# Power-SMPS.net
KiCad netlist of a schematic drawn in Altium Designer
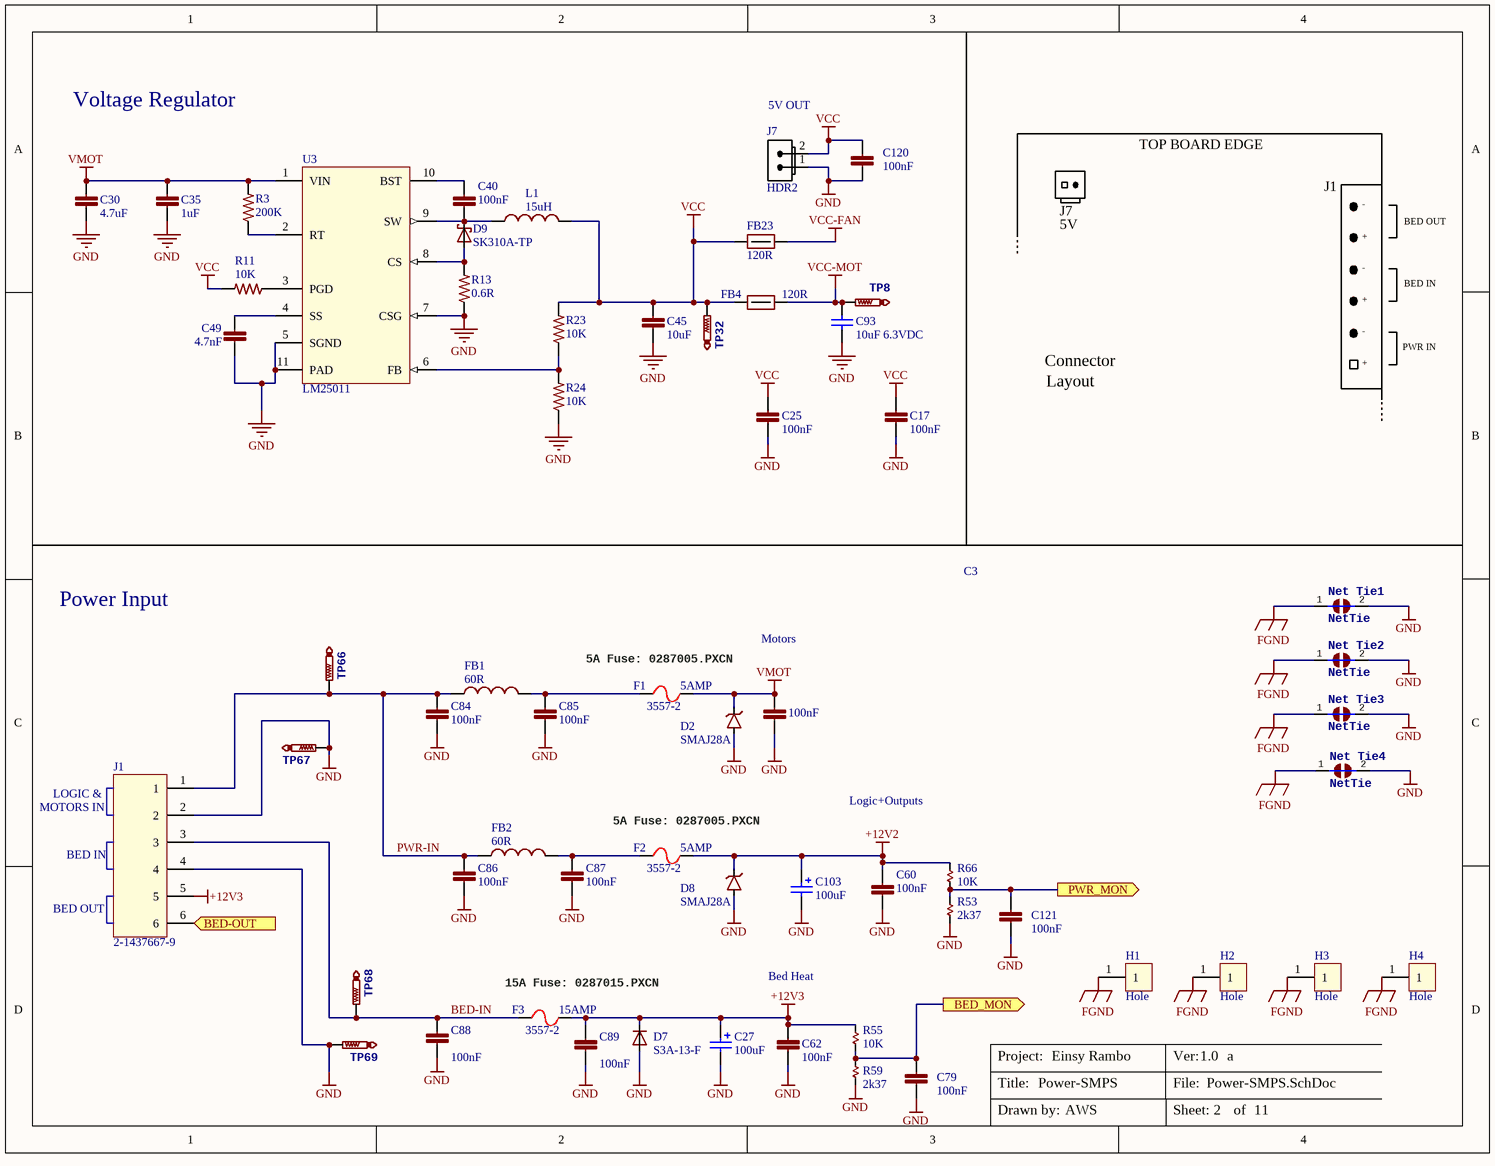
[diagram p0: Power-SMPS.SchDoc]

(export (version "E")
  (design (tool "Eeschema 10.0.6"))
  (components
    (comp (ref "C3")
      (value "100nF")
      (footprint "C0603")
      (description "CAP CER 0603 100nF 50V 10% X7R")
      (fields (field (name "MANUFACTURER") "Kemet") (field (name "TOLERANCE") "+/- 10%"))
      (libsource (lib "3Delight") (part "C0603C104K5RACTU"))
    )
    (comp (ref "C17")
      (value "100nF")
      (footprint "C0402")
      (description "CAP CER 0402 100nF 16V 10% X7R")
      (fields (field (name "MANUFACTURER") "Murata") (field (name "TOLERANCE") "+/- 10%"))
      (libsource (lib "") (part "GRM155R71C104KA88D_1"))
    )
    (comp (ref "C25")
      (value "100nF")
      (footprint "C0603")
      (description "CAP CER 0603 100nF 50V 10% X7R")
      (fields (field (name "MANUFACTURER") "Kemet") (field (name "TOLERANCE") "+/- 10%"))
      (libsource (lib "3Delight") (part "C0603C104K5RACTU"))
    )
    (comp (ref "C27")
      (value "100uF")
      (footprint "CAP-ELEC-063063077")
      (description "CAP ALUM 100UF 35V 20% SMD")
      (fields (field (name "MANUFACTURER") "Nichicon") (field (name "TOLERANCE") "+/- 20%"))
      (libsource (lib "3Delight") (part "UWT1V101MCL1GS"))
    )
    (comp (ref "C30")
      (value "4.7uF")
      (footprint "C1206")
      (description "CAP CER 1206 4.7uF 50V 10% X5R")
      (fields (field (name "MANUFACTURER") "Kemet") (field (name "TOLERANCE") "+/- 10%"))
      (libsource (lib "3Delight") (part "C1206C475K5PACTU"))
    )
    (comp (ref "C35")
      (value "1uF")
      (footprint "C0805")
      (description "CAP CER 0805 1uF 50V 10% X7R")
      (fields (field (name "MANUFACTURER") "Murata") (field (name "TOLERANCE") "+/- 10%"))
      (libsource (lib "3Delight") (part "GRM21BR71H105KA12L"))
    )
    (comp (ref "C40")
      (value "100nF")
      (footprint "C0603")
      (description "CAP CER 0603 100nF 50V 10% X7R")
      (fields (field (name "MANUFACTURER") "Kemet") (field (name "TOLERANCE") "+/- 10%"))
      (libsource (lib "3Delight") (part "C0603C104K5RACTU"))
    )
    (comp (ref "C45")
      (value "10uF")
      (footprint "C0805")
      (description "CAP CER 0805 10uF 10V 10% X5R")
      (fields (field (name "MANUFACTURER") "Kemet") (field (name "TOLERANCE") "+/- 10%"))
      (libsource (lib "3Delight") (part "C0805C106K8PACTU"))
    )
    (comp (ref "C49")
      (value "4.7nF")
      (footprint "C0402")
      (description "CAP CER 0402 4.7nF 25V 10% X7R")
      (fields (field (name "MANUFACTURER") "YAGEO") (field (name "TOLERANCE") "+/- 10%"))
      (libsource (lib "3Delight") (part "CC0402KRX7R8BB472"))
    )
    (comp (ref "C60")
      (value "100nF")
      (footprint "C0603")
      (description "CAP CER 0603 100nF 50V 10% X7R")
      (fields (field (name "MANUFACTURER") "Kemet") (field (name "TOLERANCE") "+/- 10%"))
      (libsource (lib "3Delight") (part "C0603C104K5RACTU"))
    )
    (comp (ref "C62")
      (value "100nF")
      (footprint "C0603")
      (description "CAP CER 0603 100nF 50V 10% X7R")
      (fields (field (name "MANUFACTURER") "Kemet") (field (name "TOLERANCE") "+/- 10%"))
      (libsource (lib "3Delight") (part "C0603C104K5RACTU"))
    )
    (comp (ref "C79")
      (value "100nF")
      (footprint "C0402")
      (description "CAP CER 0402 100nF 16V 10% X7R")
      (fields (field (name "MANUFACTURER") "Murata") (field (name "TOLERANCE") "+/- 10%"))
      (libsource (lib "3Delight") (part "GRM155R71C104KA88D"))
    )
    (comp (ref "C84")
      (value "100nF")
      (footprint "C0603")
      (description "CAP CER 0603 100nF 50V 10% X7R")
      (fields (field (name "MANUFACTURER") "Kemet") (field (name "TOLERANCE") "+/- 10%"))
      (libsource (lib "3Delight") (part "C0603C104K5RACTU"))
    )
    (comp (ref "C85")
      (value "100nF")
      (footprint "C0603")
      (description "CAP CER 0603 100nF 50V 10% X7R")
      (fields (field (name "MANUFACTURER") "Kemet") (field (name "TOLERANCE") "+/- 10%"))
      (libsource (lib "3Delight") (part "C0603C104K5RACTU"))
    )
    (comp (ref "C86")
      (value "100nF")
      (footprint "C0603")
      (description "CAP CER 0603 100nF 50V 10% X7R")
      (fields (field (name "MANUFACTURER") "Kemet") (field (name "TOLERANCE") "+/- 10%"))
      (libsource (lib "3Delight") (part "C0603C104K5RACTU"))
    )
    (comp (ref "C87")
      (value "100nF")
      (footprint "C0603")
      (description "CAP CER 0603 100nF 50V 10% X7R")
      (fields (field (name "MANUFACTURER") "Kemet") (field (name "TOLERANCE") "+/- 10%"))
      (libsource (lib "3Delight") (part "C0603C104K5RACTU"))
    )
    (comp (ref "C88")
      (value "100nF")
      (footprint "C0603")
      (description "CAP CER 0603 100nF 50V 10% X7R")
      (fields (field (name "MANUFACTURER") "Kemet") (field (name "TOLERANCE") "+/- 10%"))
      (libsource (lib "3Delight") (part "C0603C104K5RACTU"))
    )
    (comp (ref "C89")
      (value "100nF")
      (footprint "C0603")
      (description "CAP CER 0603 100nF 50V 10% X7R")
      (fields (field (name "MANUFACTURER") "Kemet") (field (name "TOLERANCE") "+/- 10%"))
      (libsource (lib "3Delight") (part "C0603C104K5RACTU"))
    )
    (comp (ref "C93")
      (value "10uF 6.3VDC")
      (footprint "C0603")
      (description "CAP CER 10UF 6.3V 10% JB 0603")
      (fields (field (name "TOLERANCE") "+/- 10%") (field (name "MANUFACTURER") "TDK"))
      (libsource (lib "Tigershark3D") (part "C1608JB0J106K080AB"))
    )
    (comp (ref "C103")
      (value "100uF")
      (footprint "CAP-ELEC-063063077")
      (description "CAP ALUM 100UF 35V 20% SMD")
      (fields (field (name "MANUFACTURER") "Nichicon") (field (name "TOLERANCE") "+/- 20%"))
      (libsource (lib "3Delight") (part "UWT1V101MCL1GS"))
    )
    (comp (ref "C120")
      (value "100nF")
      (footprint "C0402")
      (description "CAP CER 0402 100nF 16V 10% X7R")
      (fields (field (name "MANUFACTURER") "Murata") (field (name "TOLERANCE") "+/- 10%"))
      (libsource (lib "") (part "GRM155R71C104KA88D_2"))
    )
    (comp (ref "C121")
      (value "100nF")
      (footprint "C0402")
      (description "CAP CER 0402 100nF 16V 10% X7R")
      (fields (field (name "MANUFACTURER") "Murata") (field (name "TOLERANCE") "+/- 10%"))
      (libsource (lib "3Delight") (part "GRM155R71C104KA88D"))
    )
    (comp (ref "D2")
      (value "SMAJ28A")
      (footprint "SMA-SM")
      (description "TVS DIODE 28VWM 45.4VC SMA")
      (fields (field (name "MANUFACTURER") "Diodes Inc") (field (name "TOLERANCE") "NA"))
      (libsource (lib "Diodes") (part "SMAJ28A"))
    )
    (comp (ref "D7")
      (value "S3A-13-F")
      (footprint "DO-214AB")
      (description "DIODE DO-214AB")
      (fields (field (name "MANUFACTURER") "Diodes Incorporated") (field (name "TOLERANCE") "NA"))
      (libsource (lib "3Delight") (part "S3A-13-F"))
    )
    (comp (ref "D8")
      (value "SMAJ28A")
      (footprint "SMA-SM")
      (description "TVS DIODE 28VWM 45.4VC SMA")
      (fields (field (name "MANUFACTURER") "Diodes Inc") (field (name "TOLERANCE") "NA"))
      (libsource (lib "Diodes") (part "SMAJ28A"))
    )
    (comp (ref "D9")
      (value "SK310A-TP")
      (footprint "SMA-SM")
      (description "DIODE Schottky 3A SMA")
      (fields (field (name "MANUFACTURER") "MCC") (field (name "PART") "SK310A"))
      (libsource (lib "3Delight") (part "SK310A"))
    )
    (comp (ref "F1")
      (value "3557-2")
      (footprint "3557")
      (description "FUSE PTH ATO")
      (fields (field (name "MANUFACTURER") "Keystone") (field (name "PART") "Fuse"))
      (libsource (lib "3Delight") (part "3557-2"))
    )
    (comp (ref "F2")
      (value "3557-2")
      (footprint "3557")
      (description "FUSE PTH ATO")
      (fields (field (name "MANUFACTURER") "Keystone") (field (name "PART") "Fuse"))
      (libsource (lib "3Delight") (part "3557-2"))
    )
    (comp (ref "F3")
      (value "3557-2")
      (footprint "3557")
      (description "FUSE PTH ATO")
      (fields (field (name "MANUFACTURER") "Keystone") (field (name "PART") "Fuse"))
      (libsource (lib "3Delight") (part "3557-2"))
    )
    (comp (ref "FB1")
      (value "60R")
      (footprint "3Delight:L1806")
      (description "FERRITE BEAD 1806 60ohm")
      (fields (field (name "MANUFACTURER") "Murata") (field (name "PART") "60Rf"))
      (libsource (lib "3Delight") (part "BLM41PG600SN1L"))
    )
    (comp (ref "FB2")
      (value "60R")
      (footprint "3Delight:L1806")
      (description "FERRITE BEAD 1806 60ohm")
      (fields (field (name "MANUFACTURER") "Murata") (field (name "PART") "60Rf"))
      (libsource (lib "3Delight") (part "BLM41PG600SN1L"))
    )
    (comp (ref "FB4")
      (value "120R")
      (footprint "FB0603")
      (description "FERRITE BEAD 120 OHM 0603 1LN")
      (fields (field (name "MANUFACTURER") "Samsung") (field (name "PART") "FERRITE 120R 3A 0603"))
      (libsource (lib "3Delight") (part "FERRITE 220R 2.5A 0603"))
    )
    (comp (ref "FB23")
      (value "120R")
      (footprint "FB0603")
      (description "FERRITE BEAD 120 OHM 0603 1LN")
      (fields (field (name "MANUFACTURER") "Samsung") (field (name "PART") "FERRITE 120R 3A 0603"))
      (libsource (lib "Inductors") (part "FERRITE 120R 3A 0603"))
    )
    (comp (ref "H1")
      (value "Hole")
      (footprint "Wave_hole_3x7-singleSided")
      (libsource (lib "3Delight") (part "Hole"))
    )
    (comp (ref "H2")
      (value "Hole")
      (footprint "Wave_hole_3x7-singleSided")
      (libsource (lib "3Delight") (part "Hole"))
    )
    (comp (ref "H3")
      (value "Hole")
      (footprint "Wave_hole_3x7-singleSided")
      (libsource (lib "3Delight") (part "Hole"))
    )
    (comp (ref "H4")
      (value "Hole")
      (footprint "Wave_hole_3x7-singleSided")
      (libsource (lib "3Delight") (part "Hole"))
    )
    (comp (ref "J1")
      (value "2-1437667-9")
      (footprint "CON-Barrier-6-8.26mm")
      (description "CONN BARRIER STRIP 6CIRC 0.325\"")
      (fields (field (name "MANUFACTURER") "TE") (field (name "PART") "6POS"))
      (libsource (lib "3Delight") (part "2-1437667-9"))
    )
    (comp (ref "J7")
      (value "HDR2")
      (footprint "70543-02")
      (description "Connector 2pos")
      (fields (field (name "MANUFACTURER") "Molex") (field (name "PART") "10 Pin Conn"))
      (libsource (lib "Archim_0.4") (part "CONN 2PIN VERT 0.1{dblquote} SHRD LOCKING"))
    )
    (comp (ref "L1")
      (value "15uH")
      (footprint "XAL50xx_VLS6045")
      (description "FIXED IND 15UH 2.5A 98 MOHM SMD")
      (fields (field (name "MANUFACTURER") "TDK") (field (name "TOLERANCE") "+/- 20%"))
      (libsource (lib "3Delight") (part "IND 15uH 2.5A 0.075R"))
    )
    (comp (ref "Net Tie1")
      (value "NetTie")
      (footprint "Net Tie")
      (description "Net Tie")
      (fields (field (name "PUBLISHER") "UltiMachine"))
      (libsource (lib "3Delight") (part "NetTie"))
    )
    (comp (ref "Net Tie2")
      (value "NetTie")
      (footprint "Net Tie")
      (description "Net Tie")
      (fields (field (name "PUBLISHER") "UltiMachine"))
      (libsource (lib "3Delight") (part "NetTie"))
    )
    (comp (ref "Net Tie3")
      (value "NetTie")
      (footprint "Net Tie")
      (description "Net Tie")
      (fields (field (name "PUBLISHER") "UltiMachine"))
      (libsource (lib "3Delight") (part "NetTie"))
    )
    (comp (ref "Net Tie4")
      (value "NetTie")
      (footprint "Net Tie")
      (description "Net Tie")
      (fields (field (name "PUBLISHER") "UltiMachine"))
      (libsource (lib "3Delight") (part "NetTie"))
    )
    (comp (ref "R3")
      (value "200K")
      (footprint "R0402")
      (description "RES 0402 200K")
      (fields (field (name "MANUFACTURER") "Vishay Dale") (field (name "TOLERANCE") "+/- 1%"))
      (libsource (lib "3Delight") (part "CRCW0402200KFKED"))
    )
    (comp (ref "R11")
      (value "10K")
      (footprint "R0402")
      (description "RES SMD 10K OHM 1% 1/16W 0402")
      (fields (field (name "MANUFACTURER") "Yageo") (field (name "PART") "10k 1% 0402"))
      (libsource (lib "3Delight") (part "RC0402FR-0710KP"))
    )
    (comp (ref "R13")
      (value "0.6R")
      (footprint "2512R-0.55")
      (description "RES 0.06 OHM 1W 1% 2512 SMD")
      (fields (field (name "MANUFACTURER") "Yageo") (field (name "TOLERANCE") "1%"))
      (libsource (lib "3Delight") (part "RL2512FK-070R06L"))
    )
    (comp (ref "R23")
      (value "10K")
      (footprint "R0402")
      (description "RES SMD 10K OHM 1% 1/16W 0402")
      (fields (field (name "MANUFACTURER") "Yageo") (field (name "PART") "10k 1% 0402"))
      (libsource (lib "3Delight") (part "RC0402FR-0710KP"))
    )
    (comp (ref "R24")
      (value "10K")
      (footprint "R0402")
      (description "RES SMD 10K OHM 1% 1/16W 0402")
      (fields (field (name "MANUFACTURER") "Yageo") (field (name "PART") "10k 1% 0402"))
      (libsource (lib "3Delight") (part "RC0402FR-0710KP"))
    )
    (comp (ref "R53")
      (value "2k37")
      (footprint "R0402")
      (description "RES SMD 2.37K OHM 1% 1/16W 0402")
      (fields (field (name "MANUFACTURER") "Yageo") (field (name "PART") "2.37k"))
      (libsource (lib "3Delight") (part "RC0402FR-072K37L"))
    )
    (comp (ref "R55")
      (value "10K")
      (footprint "R0402")
      (description "RES SMD 10K OHM 1% 1/16W 0402")
      (fields (field (name "MANUFACTURER") "Yageo") (field (name "PART") "10k 1% 0402"))
      (libsource (lib "Resistors") (part "10k 1% 0402"))
    )
    (comp (ref "R59")
      (value "2k37")
      (footprint "R0402")
      (description "RES SMD 2.37K OHM 1% 1/16W 0402")
      (fields (field (name "MANUFACTURER") "Yageo") (field (name "PART") "2.37k"))
      (libsource (lib "3Delight") (part "RC0402FR-072K37L"))
    )
    (comp (ref "R66")
      (value "10K")
      (footprint "R0402")
      (description "RES SMD 10K OHM 1% 1/16W 0402")
      (fields (field (name "MANUFACTURER") "Yageo") (field (name "PART") "10k 1% 0402"))
      (libsource (lib "Resistors") (part "10k 1% 0402"))
    )
    (comp (ref "TP8")
      (value "TestPoint")
      (footprint "TP1-27")
      (description "Test Point")
      (libsource (lib "") (part "TestPoint_1"))
    )
    (comp (ref "TP32")
      (value "TestPoint")
      (footprint "TP1-27")
      (description "Test Point")
      (libsource (lib "3Delight") (part "TestPoint"))
    )
    (comp (ref "TP66")
      (value "TestPoint")
      (footprint "TP1-27")
      (description "Test Point")
      (libsource (lib "") (part "TestPoint_2"))
    )
    (comp (ref "TP67")
      (value "TestPoint")
      (footprint "TP1-27")
      (description "Test Point")
      (libsource (lib "") (part "TestPoint_3"))
    )
    (comp (ref "TP68")
      (value "TestPoint")
      (footprint "TP1-27")
      (description "Test Point")
      (libsource (lib "") (part "TestPoint_2"))
    )
    (comp (ref "TP69")
      (value "TestPoint")
      (footprint "TP1-27")
      (description "Test Point")
      (libsource (lib "") (part "TestPoint_1"))
    )
    (comp (ref "U3")
      (value "LM25011")
      (footprint "VSSOP10")
      (description "REG BUCK")
      (fields (field (name "MANUFACTURER") "TI") (field (name "TOLERANCE") "NA"))
      (libsource (lib "3Delight") (part "LM25011"))
    )
  )
  (nets
    (net (code "1") (name "+12V2") (class "Default")
      (node (ref "C103") (pin "1") (pinfunction "1_1") (pintype "passive"))
      (node (ref "C60") (pin "1") (pinfunction "1_1") (pintype "passive"))
      (node (ref "D8") (pin "K") (pinfunction "K_K") (pintype "passive"))
      (node (ref "F2") (pin "2") (pinfunction "2_2") (pintype "passive"))
      (node (ref "R66") (pin "2") (pinfunction "2_2") (pintype "passive"))
    )
    (net (code "2") (name "+12V3") (class "Default")
      (node (ref "C27") (pin "1") (pinfunction "1_1") (pintype "passive"))
      (node (ref "C62") (pin "1") (pinfunction "1_1") (pintype "passive"))
      (node (ref "C89") (pin "1") (pinfunction "1_1") (pintype "passive"))
      (node (ref "D7") (pin "C") (pinfunction "C_C") (pintype "passive"))
      (node (ref "F3") (pin "2") (pinfunction "2_2") (pintype "passive"))
      (node (ref "J1") (pin "5") (pinfunction "5_5") (pintype "passive"))
      (node (ref "R55") (pin "2") (pinfunction "2_2") (pintype "passive"))
    )
    (net (code "3") (name "/BED-IN") (class "Default")
      (node (ref "C88") (pin "1") (pinfunction "1_1") (pintype "passive"))
      (node (ref "F3") (pin "1") (pinfunction "1_1") (pintype "passive"))
      (node (ref "J1") (pin "3") (pinfunction "3_3") (pintype "passive"))
      (node (ref "TP68") (pin "TP") (pinfunction "TP_TP") (pintype "passive"))
    )
    (net (code "4") (name "/BED-OUT") (class "Default")
      (node (ref "J1") (pin "6") (pinfunction "6_6") (pintype "passive"))
    )
    (net (code "5") (name "/BED_MON") (class "Default")
      (node (ref "C79") (pin "1") (pinfunction "1_1") (pintype "passive"))
      (node (ref "R55") (pin "1") (pinfunction "1_1") (pintype "passive"))
      (node (ref "R59") (pin "1") (pinfunction "1_1") (pintype "passive"))
    )
    (net (code "6") (name "/PWR-IN") (class "Default")
      (node (ref "C84") (pin "1") (pinfunction "1_1") (pintype "passive"))
      (node (ref "C86") (pin "1") (pinfunction "1_1") (pintype "passive"))
      (node (ref "FB1") (pin "1") (pinfunction "1_1") (pintype "passive"))
      (node (ref "FB2") (pin "1") (pinfunction "1_1") (pintype "passive"))
      (node (ref "J1") (pin "1") (pinfunction "1_1") (pintype "passive"))
      (node (ref "TP66") (pin "TP") (pinfunction "TP_TP") (pintype "passive"))
    )
    (net (code "7") (name "/PWR_MON") (class "Default")
      (node (ref "C121") (pin "1") (pinfunction "1_1") (pintype "passive"))
      (node (ref "R53") (pin "1") (pinfunction "1_1") (pintype "passive"))
      (node (ref "R66") (pin "1") (pinfunction "1_1") (pintype "passive"))
    )
    (net (code "8") (name "FGND") (class "Default")
      (node (ref "H1") (pin "1") (pinfunction "1_1") (pintype "power_in"))
      (node (ref "H2") (pin "1") (pinfunction "1_1") (pintype "power_in"))
      (node (ref "H3") (pin "1") (pinfunction "1_1") (pintype "power_in"))
      (node (ref "H4") (pin "1") (pinfunction "1_1") (pintype "power_in"))
      (node (ref "Net Tie1") (pin "1") (pinfunction "1_1") (pintype "passive"))
      (node (ref "Net Tie2") (pin "1") (pinfunction "1_1") (pintype "passive"))
      (node (ref "Net Tie3") (pin "1") (pinfunction "1_1") (pintype "passive"))
      (node (ref "Net Tie4") (pin "1") (pinfunction "1_1") (pintype "passive"))
    )
    (net (code "9") (name "GND") (class "Default")
      (node (ref "C103") (pin "2") (pinfunction "2_2") (pintype "passive"))
      (node (ref "C120") (pin "1") (pinfunction "1_1") (pintype "passive"))
      (node (ref "C121") (pin "2") (pinfunction "2_2") (pintype "passive"))
      (node (ref "C17") (pin "2") (pinfunction "2_2") (pintype "passive"))
      (node (ref "C25") (pin "2") (pinfunction "2_2") (pintype "passive"))
      (node (ref "C27") (pin "2") (pinfunction "2_2") (pintype "passive"))
      (node (ref "C3") (pin "2") (pinfunction "2_2") (pintype "passive"))
      (node (ref "C30") (pin "2") (pinfunction "2_2") (pintype "passive"))
      (node (ref "C35") (pin "2") (pinfunction "2_2") (pintype "passive"))
      (node (ref "C45") (pin "2") (pinfunction "2_2") (pintype "passive"))
      (node (ref "C49") (pin "2") (pinfunction "2_2") (pintype "passive"))
      (node (ref "C60") (pin "2") (pinfunction "2_2") (pintype "passive"))
      (node (ref "C62") (pin "2") (pinfunction "2_2") (pintype "passive"))
      (node (ref "C79") (pin "2") (pinfunction "2_2") (pintype "passive"))
      (node (ref "C84") (pin "2") (pinfunction "2_2") (pintype "passive"))
      (node (ref "C85") (pin "2") (pinfunction "2_2") (pintype "passive"))
      (node (ref "C86") (pin "2") (pinfunction "2_2") (pintype "passive"))
      (node (ref "C87") (pin "2") (pinfunction "2_2") (pintype "passive"))
      (node (ref "C88") (pin "2") (pinfunction "2_2") (pintype "passive"))
      (node (ref "C89") (pin "2") (pinfunction "2_2") (pintype "passive"))
      (node (ref "C93") (pin "1") (pinfunction "1_1") (pintype "passive"))
      (node (ref "D2") (pin "A") (pinfunction "A_A") (pintype "passive"))
      (node (ref "D7") (pin "A") (pinfunction "A_A") (pintype "passive"))
      (node (ref "D8") (pin "A") (pinfunction "A_A") (pintype "passive"))
      (node (ref "J1") (pin "2") (pinfunction "2_2") (pintype "passive"))
      (node (ref "J1") (pin "4") (pinfunction "4_4") (pintype "passive"))
      (node (ref "J7") (pin "1") (pinfunction "S_1") (pintype "passive"))
      (node (ref "Net Tie1") (pin "2") (pinfunction "2_2") (pintype "passive"))
      (node (ref "Net Tie2") (pin "2") (pinfunction "2_2") (pintype "passive"))
      (node (ref "Net Tie3") (pin "2") (pinfunction "2_2") (pintype "passive"))
      (node (ref "Net Tie4") (pin "2") (pinfunction "2_2") (pintype "passive"))
      (node (ref "R13") (pin "1") (pinfunction "1_1") (pintype "passive"))
      (node (ref "R24") (pin "1") (pinfunction "1_1") (pintype "passive"))
      (node (ref "R53") (pin "2") (pinfunction "2_2") (pintype "passive"))
      (node (ref "R59") (pin "2") (pinfunction "2_2") (pintype "passive"))
      (node (ref "TP67") (pin "TP") (pinfunction "TP_TP") (pintype "passive"))
      (node (ref "TP69") (pin "TP") (pinfunction "TP_TP") (pintype "passive"))
      (node (ref "U3") (pin "11") (pinfunction "PAD_11") (pintype "power_in"))
      (node (ref "U3") (pin "5") (pinfunction "SGND_5") (pintype "power_in"))
      (node (ref "U3") (pin "7") (pinfunction "CSG_7") (pintype "input"))
    )
    (net (code "10") (name "Net-(C85-Pad1)") (class "Default")
      (node (ref "C85") (pin "1") (pinfunction "1_1") (pintype "passive"))
      (node (ref "F1") (pin "1") (pinfunction "1_1") (pintype "passive"))
      (node (ref "FB1") (pin "2") (pinfunction "2_2") (pintype "passive"))
    )
    (net (code "11") (name "Net-(C87-Pad1)") (class "Default")
      (node (ref "C87") (pin "1") (pinfunction "1_1") (pintype "passive"))
      (node (ref "F2") (pin "1") (pinfunction "1_1") (pintype "passive"))
      (node (ref "FB2") (pin "2") (pinfunction "2_2") (pintype "passive"))
    )
    (net (code "12") (name "Net-(U3-BST)") (class "Default")
      (node (ref "C40") (pin "1") (pinfunction "1_1") (pintype "passive"))
      (node (ref "U3") (pin "10") (pinfunction "BST_10") (pintype "power_in"))
    )
    (net (code "13") (name "Net-(U3-CS)") (class "Default")
      (node (ref "D9") (pin "A") (pinfunction "A_A") (pintype "passive"))
      (node (ref "R13") (pin "2") (pinfunction "2_2") (pintype "passive"))
      (node (ref "U3") (pin "8") (pinfunction "CS_8") (pintype "input"))
    )
    (net (code "14") (name "Net-(U3-FB)") (class "Default")
      (node (ref "R23") (pin "1") (pinfunction "1_1") (pintype "passive"))
      (node (ref "R24") (pin "2") (pinfunction "2_2") (pintype "passive"))
      (node (ref "U3") (pin "6") (pinfunction "FB_6") (pintype "input"))
    )
    (net (code "15") (name "Net-(U3-PGD)") (class "Default")
      (node (ref "R11") (pin "1") (pinfunction "1_1") (pintype "passive"))
      (node (ref "U3") (pin "3") (pinfunction "PGD_3") (pintype "power_in"))
    )
    (net (code "16") (name "Net-(U3-RT)") (class "Default")
      (node (ref "R3") (pin "1") (pinfunction "1_1") (pintype "passive"))
      (node (ref "U3") (pin "2") (pinfunction "RT_2") (pintype "power_in"))
    )
    (net (code "17") (name "Net-(U3-SS)") (class "Default")
      (node (ref "C49") (pin "1") (pinfunction "1_1") (pintype "passive"))
      (node (ref "U3") (pin "4") (pinfunction "SS_4") (pintype "power_in"))
    )
    (net (code "18") (name "Net-(U3-SW)") (class "Default")
      (node (ref "C40") (pin "2") (pinfunction "2_2") (pintype "passive"))
      (node (ref "D9") (pin "C") (pinfunction "C_C") (pintype "passive"))
      (node (ref "L1") (pin "1") (pinfunction "1_1") (pintype "passive"))
      (node (ref "U3") (pin "9") (pinfunction "SW_9") (pintype "output"))
    )
    (net (code "19") (name "VCC") (class "Default")
      (node (ref "C120") (pin "2") (pinfunction "2_2") (pintype "passive"))
      (node (ref "C17") (pin "1") (pinfunction "1_1") (pintype "passive"))
      (node (ref "C25") (pin "1") (pinfunction "1_1") (pintype "passive"))
      (node (ref "C45") (pin "1") (pinfunction "1_1") (pintype "passive"))
      (node (ref "FB23") (pin "1") (pinfunction "1_1") (pintype "passive"))
      (node (ref "FB4") (pin "1") (pinfunction "1_1") (pintype "passive"))
      (node (ref "J7") (pin "2") (pinfunction "S_2") (pintype "passive"))
      (node (ref "L1") (pin "2") (pinfunction "2_2") (pintype "passive"))
      (node (ref "R11") (pin "2") (pinfunction "2_2") (pintype "passive"))
      (node (ref "R23") (pin "2") (pinfunction "2_2") (pintype "passive"))
      (node (ref "TP32") (pin "TP") (pinfunction "TP_TP") (pintype "passive"))
    )
    (net (code "20") (name "VCC-FAN") (class "Default")
      (node (ref "FB23") (pin "2") (pinfunction "2_2") (pintype "passive"))
    )
    (net (code "21") (name "VCC-MOT") (class "Default")
      (node (ref "C93") (pin "2") (pinfunction "2_2") (pintype "passive"))
      (node (ref "FB4") (pin "2") (pinfunction "2_2") (pintype "passive"))
      (node (ref "TP8") (pin "TP") (pinfunction "TP_TP") (pintype "passive"))
    )
    (net (code "22") (name "VMOT") (class "Default")
      (node (ref "C3") (pin "1") (pinfunction "1_1") (pintype "passive"))
      (node (ref "C30") (pin "1") (pinfunction "1_1") (pintype "passive"))
      (node (ref "C35") (pin "1") (pinfunction "1_1") (pintype "passive"))
      (node (ref "D2") (pin "K") (pinfunction "K_K") (pintype "passive"))
      (node (ref "F1") (pin "2") (pinfunction "2_2") (pintype "passive"))
      (node (ref "R3") (pin "2") (pinfunction "2_2") (pintype "passive"))
      (node (ref "U3") (pin "1") (pinfunction "VIN_1") (pintype "power_in"))
    )
  )
)
